# SW108_0713.net
KiCad netlist of a schematic drawn in Altium Designer
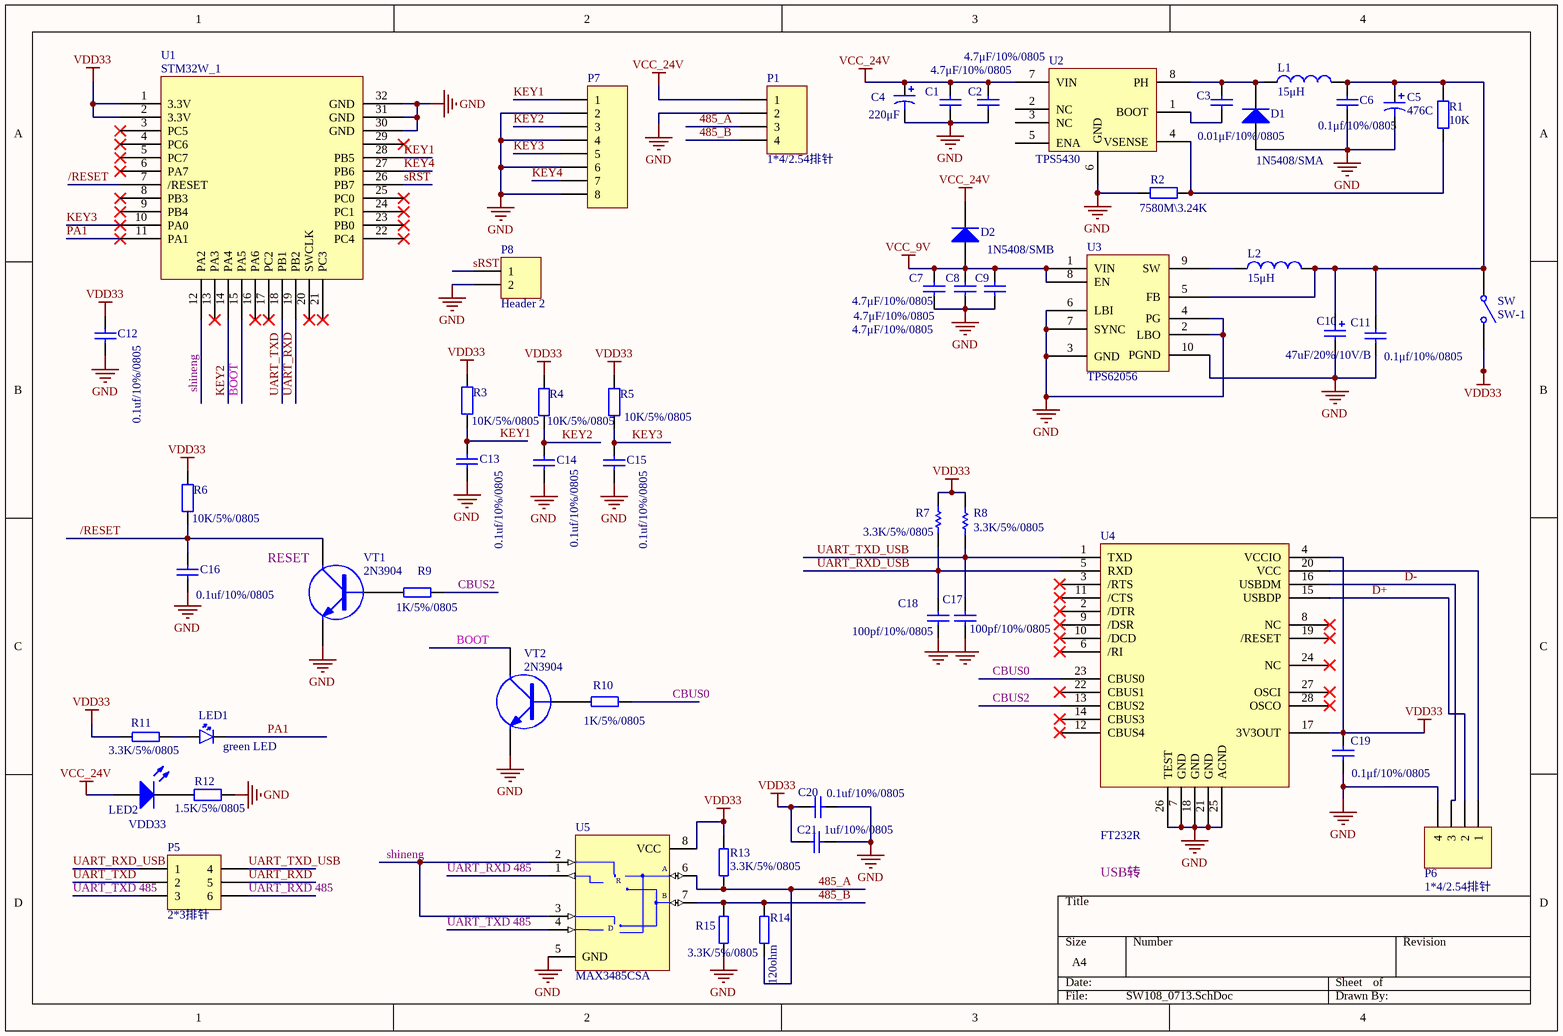
[diagram p0: SW108_0713.SchDoc]

(export (version "E")
  (design (tool "Eeschema 10.0.6"))
  (components
    (comp (ref "C1")
      (value "4.7μF/10%/0805")
      (footprint "C-0805")
      (description "Capacitor")
      (fields (field (name "PUBLISHER") "Altium Limited"))
      (libsource (lib "Miscellaneous Devices") (part "Cap"))
    )
    (comp (ref "C2")
      (value "4.7μF/10%/0805")
      (footprint "C-0805")
      (description "Capacitor")
      (fields (field (name "PUBLISHER") "Altium Limited"))
      (libsource (lib "Miscellaneous Devices") (part "Cap"))
    )
    (comp (ref "C3")
      (value "0.01μF/10%/0805")
      (footprint "C-0805")
      (description "Capacitor")
      (fields (field (name "PUBLISHER") "Altium Limited"))
      (libsource (lib "Miscellaneous Devices") (part "Cap"))
    )
    (comp (ref "C4")
      (value "220μF")
      (footprint "CZ3.0/6.5")
      (description "Polarized Capacitor (Radial)")
      (fields (field (name "PUBLISHER") "Altium Limited"))
      (libsource (lib "Miscellaneous Devices") (part "Cap Pol1"))
    )
    (comp (ref "C5")
      (value "476C")
      (footprint "C-TAN-D")
      (description "Polarized Capacitor (Radial)")
      (fields (field (name "PUBLISHER") "Altium Limited"))
      (libsource (lib "Miscellaneous Devices") (part "Cap Pol1"))
    )
    (comp (ref "C6")
      (value "0.1μf/10%/0805")
      (footprint "C-0805")
      (description "Capacitor")
      (fields (field (name "PUBLISHER") "Altium Limited"))
      (libsource (lib "Miscellaneous Devices") (part "Cap"))
    )
    (comp (ref "C7")
      (value "4.7μF/10%/0805")
      (footprint "C-0805")
      (description "Capacitor")
      (fields (field (name "PUBLISHER") "Altium Limited"))
      (libsource (lib "Miscellaneous Devices") (part "Cap"))
    )
    (comp (ref "C8")
      (value "4.7μF/10%/0805")
      (footprint "C-0805")
      (description "Capacitor")
      (fields (field (name "PUBLISHER") "Altium Limited"))
      (libsource (lib "Miscellaneous Devices") (part "Cap"))
    )
    (comp (ref "C9")
      (value "4.7μF/10%/0805")
      (footprint "C-0805")
      (description "Capacitor")
      (fields (field (name "PUBLISHER") "Altium Limited"))
      (libsource (lib "Miscellaneous Devices") (part "Cap"))
    )
    (comp (ref "C10")
      (value "47uF/20%/10V/B")
      (footprint "C-TAN-B")
      (libsource (lib "浙江关西电机数据库") (part "CAP_polarity"))
    )
    (comp (ref "C11")
      (value "0.1μf/10%/0805")
      (footprint "C-0805")
      (description "Capacitor")
      (fields (field (name "PUBLISHER") "Altium Limited"))
      (libsource (lib "Miscellaneous Devices") (part "Cap"))
    )
    (comp (ref "C12")
      (value "0.1uf/10%/0805")
      (footprint "C-0805")
      (description "Capacitor")
      (fields (field (name "PUBLISHER") "Altium Limited"))
      (libsource (lib "Miscellaneous Devices") (part "Cap"))
    )
    (comp (ref "C13")
      (value "0.1uf/10%/0805")
      (footprint "C-0805")
      (description "Capacitor")
      (fields (field (name "PUBLISHER") "Altium Limited"))
      (libsource (lib "Miscellaneous Devices") (part "Cap"))
    )
    (comp (ref "C14")
      (value "0.1uf/10%/0805")
      (footprint "C-0805")
      (description "Capacitor")
      (fields (field (name "PUBLISHER") "Altium Limited"))
      (libsource (lib "Miscellaneous Devices") (part "Cap"))
    )
    (comp (ref "C15")
      (value "0.1uf/10%/0805")
      (footprint "C-0805")
      (description "Capacitor")
      (fields (field (name "PUBLISHER") "Altium Limited"))
      (libsource (lib "Miscellaneous Devices") (part "Cap"))
    )
    (comp (ref "C16")
      (value "0.1uf/10%/0805")
      (footprint "C-0805")
      (description "Capacitor")
      (fields (field (name "PUBLISHER") "Altium Limited"))
      (libsource (lib "Miscellaneous Devices") (part "Cap"))
    )
    (comp (ref "C17")
      (value "100pf/10%/0805")
      (footprint "C-0805")
      (description "Capacitor")
      (fields (field (name "PUBLISHER") "Altium Limited"))
      (libsource (lib "Miscellaneous Devices") (part "Cap"))
    )
    (comp (ref "C18")
      (value "100pf/10%/0805")
      (footprint "C-0805")
      (description "Capacitor")
      (fields (field (name "PUBLISHER") "Altium Limited"))
      (libsource (lib "Miscellaneous Devices") (part "Cap"))
    )
    (comp (ref "C19")
      (value "0.1μf/10%/0805")
      (footprint "C-0805")
      (description "Capacitor")
      (fields (field (name "PUBLISHER") "Altium Limited"))
      (libsource (lib "Miscellaneous Devices") (part "Cap"))
    )
    (comp (ref "C20")
      (value "0.1uf/10%/0805")
      (footprint "C-0805")
      (description "Capacitor")
      (fields (field (name "PUBLISHER") "Altium Limited"))
      (libsource (lib "Miscellaneous Devices") (part "Cap"))
    )
    (comp (ref "C21")
      (value "1uf/10%/0805")
      (footprint "C-0805")
      (description "Capacitor")
      (fields (field (name "PUBLISHER") "Altium Limited"))
      (libsource (lib "Miscellaneous Devices") (part "Cap"))
    )
    (comp (ref "D1")
      (value "1N5408/SMA")
      (footprint "SMA 2+")
      (description "3 Amp Medium Power Silicon Rectifier Diode")
      (fields (field (name "PUBLISHER") "Altium Limited"))
      (libsource (lib "Miscellaneous Devices") (part "Diode 1N5408"))
    )
    (comp (ref "D2")
      (value "1N5408/SMB")
      (footprint "smb")
      (description "3 Amp Medium Power Silicon Rectifier Diode")
      (fields (field (name "PUBLISHER") "Altium Limited"))
      (libsource (lib "Miscellaneous Devices") (part "Diode 1N5408"))
    )
    (comp (ref "L1")
      (value "15μH")
      (footprint "GSDS104C2")
      (description "Inductor")
      (fields (field (name "PUBLISHER") "Altium Limited"))
      (libsource (lib "Miscellaneous Devices") (part "Inductor"))
    )
    (comp (ref "L2")
      (value "15μH")
      (footprint "GSDS104C2")
      (description "Inductor")
      (fields (field (name "PUBLISHER") "Altium Limited"))
      (libsource (lib "Miscellaneous Devices") (part "Inductor"))
    )
    (comp (ref "LED1") (value "green LED") (footprint "LED-φ3") (libsource (lib "Haze") (part "LED")))
    (comp (ref "LED2")
      (value "VDD33")
      (footprint "LED-φ3")
      (description "Typical BLUE SiC LED")
      (fields (field (name "PUBLISHER") "Altium Limited"))
      (libsource (lib "Miscellaneous Devices") (part "LED3"))
    )
    (comp (ref "P1")
      (value "1*4/2.54排针")
      (footprint "PIN-S-2.54-1*4")
      (description "Header, 4-Pin")
      (fields (field (name "PUBLISHER") "Altium Limited"))
      (libsource (lib "") (part "Header 4_1"))
    )
    (comp (ref "P5")
      (value "2*3排针")
      (footprint "HDR2X3_CEN")
      (description "Header, 3-Pin, Dual row")
      (fields (field (name "PUBLISHER") "Altium Limited"))
      (libsource (lib "Miscellaneous Connectors") (part "Header 3X2A"))
    )
    (comp (ref "P6")
      (value "1*4/2.54排针")
      (footprint "PIN-S-2.54-1*4")
      (description "Header, 4-Pin")
      (fields (field (name "PUBLISHER") "Altium Limited"))
      (libsource (lib "Miscellaneous Connectors") (part "Header 4"))
    )
    (comp (ref "P7")
      (value "Header 8")
      (footprint "HDR1X8")
      (description "Header, 8-Pin")
      (fields (field (name "PUBLISHER") "Altium Limited"))
      (libsource (lib "Miscellaneous Connectors") (part "Header 8"))
    )
    (comp (ref "P8")
      (value "Header 2")
      (footprint "HDR1X2")
      (description "Header, 2-Pin")
      (fields (field (name "PUBLISHER") "Altium Limited"))
      (libsource (lib "Miscellaneous Connectors") (part "Header 2"))
    )
    (comp (ref "R1")
      (value "10K")
      (footprint "R-0805")
      (description "Resistor")
      (fields (field (name "PUBLISHER") "Altium Limited"))
      (libsource (lib "Miscellaneous Devices") (part "Res2"))
    )
    (comp (ref "R2")
      (value "7580~{M}3.24K")
      (footprint "R-0805")
      (description "Resistor")
      (fields (field (name "PUBLISHER") "Altium Limited"))
      (libsource (lib "") (part "Res2_1"))
    )
    (comp (ref "R3")
      (value "10K/5%/0805")
      (footprint "R-0805")
      (description "Resistor")
      (fields (field (name "PUBLISHER") "Altium Limited"))
      (libsource (lib "Miscellaneous Devices") (part "Res2"))
    )
    (comp (ref "R4")
      (value "10K/5%/0805")
      (footprint "R-0805")
      (description "Resistor")
      (fields (field (name "PUBLISHER") "Altium Limited"))
      (libsource (lib "Miscellaneous Devices") (part "Res2"))
    )
    (comp (ref "R5")
      (value "10K/5%/0805")
      (footprint "R-0805")
      (description "Resistor")
      (fields (field (name "PUBLISHER") "Altium Limited"))
      (libsource (lib "Miscellaneous Devices") (part "Res2"))
    )
    (comp (ref "R6")
      (value "10K/5%/0805")
      (footprint "R-0805")
      (description "Resistor")
      (fields (field (name "PUBLISHER") "Altium Limited"))
      (libsource (lib "Miscellaneous Devices") (part "Res2"))
    )
    (comp (ref "R7")
      (value "3.3K/5%/0805")
      (footprint "R-0805")
      (libsource (lib "SCHLIBRARIES") (part "RES_1"))
    )
    (comp (ref "R8")
      (value "3.3K/5%/0805")
      (footprint "R-0805")
      (libsource (lib "SCHLIBRARIES") (part "RES_1"))
    )
    (comp (ref "R9")
      (value "1K/5%/0805")
      (footprint "R-0805")
      (description "R")
      (libsource (lib "Haze") (part "RES"))
    )
    (comp (ref "R10")
      (value "1K/5%/0805")
      (footprint "R-0805")
      (description "R")
      (libsource (lib "Haze") (part "RES"))
    )
    (comp (ref "R11")
      (value "3.3K/5%/0805")
      (footprint "R-0805")
      (description "R")
      (libsource (lib "Haze") (part "RES"))
    )
    (comp (ref "R12")
      (value "1.5K/5%/0805")
      (footprint "R-0805")
      (description "Resistor")
      (fields (field (name "PUBLISHER") "Altium Limited"))
      (libsource (lib "") (part "Res2_1"))
    )
    (comp (ref "R13")
      (value "3.3K/5%/0805")
      (footprint "R-0805")
      (description "R")
      (libsource (lib "Haze") (part "RES"))
    )
    (comp (ref "R14")
      (value "120ohm")
      (footprint "R-0805")
      (description "R")
      (libsource (lib "Haze") (part "RES"))
    )
    (comp (ref "R15")
      (value "3.3K/5%/0805")
      (footprint "R-0805")
      (description "R")
      (libsource (lib "Haze") (part "RES"))
    )
    (comp (ref "SW")
      (value "SW-1")
      (footprint "PIN-S-2.54-1*2")
      (libsource (lib "SCHLIBRARIES") (part "SW-1"))
    )
    (comp (ref "U1")
      (value "STM32W_1")
      (footprint "STM32W108-3")
      (libsource (lib "STM32W108-3") (part "STM32W108-3"))
    )
    (comp (ref "U2") (value "TPS5430") (footprint "SO-G8") (libsource (lib "SCHLIBRARIES") (part "TPS5430")))
    (comp (ref "U3")
      (value "TPS62056")
      (footprint "MSOP-10")
      (libsource (lib "SCHLIBRARIES") (part "TPS62056"))
    )
    (comp (ref "U4") (value "FT232R") (footprint "SSOP-28") (libsource (lib "Haze") (part "FT232R")))
    (comp (ref "U5")
      (value "MAX3485CSA")
      (footprint "SO-G8")
      (description "Low-Power, Slew-Rate-Limited RS-485/RS-422 Transceiver")
      (fields (field (name "PUBLISHER") "Altium Limited"))
      (libsource (lib "Maxim Communication Transceiver") (part "MAX485CSA"))
    )
    (comp (ref "VT1")
      (value "2N3904")
      (footprint "SOT23-3")
      (description "NPN Transistor")
      (libsource (lib "Haze") (part "NPN"))
    )
    (comp (ref "VT2")
      (value "2N3904")
      (footprint "SOT23-3")
      (description "NPN Transistor")
      (libsource (lib "Haze") (part "NPN"))
    )
  )
  (nets
    (net (code "1") (name "/485_A") (class "Default")
      (node (ref "P1") (pin "3") (pinfunction "3_3") (pintype "passive"))
      (node (ref "R13") (pin "1") (pinfunction "1_1") (pintype "passive"))
      (node (ref "R14") (pin "2") (pinfunction "2_2") (pintype "passive"))
      (node (ref "U5") (pin "6") (pinfunction "A_6") (pintype "bidirectional"))
    )
    (net (code "2") (name "/485_B") (class "Default")
      (node (ref "P1") (pin "4") (pinfunction "4_4") (pintype "passive"))
      (node (ref "R14") (pin "1") (pinfunction "1_1") (pintype "passive"))
      (node (ref "R15") (pin "2") (pinfunction "2_2") (pintype "passive"))
      (node (ref "U5") (pin "7") (pinfunction "B_7") (pintype "bidirectional"))
    )
    (net (code "3") (name "/BOOT") (class "Default")
      (node (ref "U1") (pin "15") (pinfunction "PA5_15") (pintype "passive"))
      (node (ref "VT2") (pin "3") (pinfunction "C_3") (pintype "passive"))
    )
    (net (code "4") (name "/CBUS0") (class "Default")
      (node (ref "R10") (pin "2") (pinfunction "2_2") (pintype "passive"))
      (node (ref "U4") (pin "23") (pinfunction "CBUS0_23") (pintype "passive"))
    )
    (net (code "5") (name "/CBUS2") (class "Default")
      (node (ref "R9") (pin "2") (pinfunction "2_2") (pintype "passive"))
      (node (ref "U4") (pin "13") (pinfunction "CBUS2_13") (pintype "passive"))
    )
    (net (code "6") (name "/D+") (class "Default")
      (node (ref "P6") (pin "2") (pinfunction "2_2") (pintype "passive"))
      (node (ref "U4") (pin "15") (pinfunction "USBDP_15") (pintype "passive"))
    )
    (net (code "7") (name "/D-") (class "Default")
      (node (ref "P6") (pin "3") (pinfunction "3_3") (pintype "passive"))
      (node (ref "U4") (pin "16") (pinfunction "USBDM_16") (pintype "passive"))
    )
    (net (code "8") (name "/KEY1") (class "Default")
      (node (ref "C13") (pin "2") (pinfunction "2_2") (pintype "passive"))
      (node (ref "P7") (pin "1") (pinfunction "1_1") (pintype "passive"))
      (node (ref "R3") (pin "1") (pinfunction "1_1") (pintype "passive"))
      (node (ref "U1") (pin "28") (pinfunction "PB5_28") (pintype "passive"))
    )
    (net (code "9") (name "/KEY2") (class "Default")
      (node (ref "C14") (pin "2") (pinfunction "2_2") (pintype "passive"))
      (node (ref "P7") (pin "3") (pinfunction "3_3") (pintype "passive"))
      (node (ref "R4") (pin "1") (pinfunction "1_1") (pintype "passive"))
      (node (ref "U1") (pin "14") (pinfunction "PA4_14") (pintype "passive"))
    )
    (net (code "10") (name "/KEY3") (class "Default")
      (node (ref "C15") (pin "2") (pinfunction "2_2") (pintype "passive"))
      (node (ref "P7") (pin "5") (pinfunction "5_5") (pintype "passive"))
      (node (ref "R5") (pin "1") (pinfunction "1_1") (pintype "passive"))
      (node (ref "U1") (pin "10") (pinfunction "PA0_10") (pintype "passive"))
    )
    (net (code "11") (name "/KEY4") (class "Default")
      (node (ref "P7") (pin "7") (pinfunction "7_7") (pintype "passive"))
      (node (ref "U1") (pin "27") (pinfunction "PB6_27") (pintype "passive"))
    )
    (net (code "12") (name "/PA1") (class "Default")
      (node (ref "LED1") (pin "2") (pinfunction "K_2") (pintype "passive"))
      (node (ref "U1") (pin "11") (pinfunction "PA1_11") (pintype "passive"))
    )
    (net (code "13") (name "/UART_RXD") (class "Default")
      (node (ref "P5") (pin "5") (pinfunction "5_5") (pintype "passive"))
      (node (ref "U1") (pin "19") (pinfunction "PB2_19") (pintype "passive"))
    )
    (net (code "14") (name "/UART_RXD 485") (class "Default")
      (node (ref "P5") (pin "6") (pinfunction "6_6") (pintype "passive"))
      (node (ref "U5") (pin "1") (pinfunction "RO_1") (pintype "output"))
    )
    (net (code "15") (name "/UART_RXD_USB") (class "Default")
      (node (ref "C18") (pin "2") (pinfunction "2_2") (pintype "passive"))
      (node (ref "P5") (pin "1") (pinfunction "1_1") (pintype "passive"))
      (node (ref "R7") (pin "1") (pinfunction "1_1") (pintype "passive"))
      (node (ref "U4") (pin "5") (pinfunction "RXD_5") (pintype "passive"))
    )
    (net (code "16") (name "/UART_TXD") (class "Default")
      (node (ref "P5") (pin "2") (pinfunction "2_2") (pintype "passive"))
      (node (ref "U1") (pin "18") (pinfunction "PB1_18") (pintype "passive"))
    )
    (net (code "17") (name "/UART_TXD 485") (class "Default")
      (node (ref "P5") (pin "3") (pinfunction "3_3") (pintype "passive"))
      (node (ref "U5") (pin "4") (pinfunction "DI_4") (pintype "input"))
    )
    (net (code "18") (name "/UART_TXD_USB") (class "Default")
      (node (ref "C17") (pin "2") (pinfunction "2_2") (pintype "passive"))
      (node (ref "P5") (pin "4") (pinfunction "4_4") (pintype "passive"))
      (node (ref "R8") (pin "1") (pinfunction "1_1") (pintype "passive"))
      (node (ref "U4") (pin "1") (pinfunction "TXD_1") (pintype "passive"))
    )
    (net (code "19") (name "/sRST") (class "Default")
      (node (ref "P8") (pin "1") (pinfunction "1_1") (pintype "passive"))
      (node (ref "U1") (pin "26") (pinfunction "PB7_26") (pintype "passive"))
    )
    (net (code "20") (name "/shineng") (class "Default")
      (node (ref "U1") (pin "12") (pinfunction "PA2_12") (pintype "passive"))
      (node (ref "U5") (pin "2") (pinfunction "~{RE}_2") (pintype "input"))
      (node (ref "U5") (pin "3") (pinfunction "DE_3") (pintype "input"))
    )
    (net (code "21") (name "/{slash}RESET") (class "Default")
      (node (ref "C16") (pin "2") (pinfunction "2_2") (pintype "passive"))
      (node (ref "R6") (pin "1") (pinfunction "1_1") (pintype "passive"))
      (node (ref "U1") (pin "7") (pinfunction "/RESET_7") (pintype "passive"))
      (node (ref "VT1") (pin "3") (pinfunction "C_3") (pintype "passive"))
    )
    (net (code "22") (name "GND") (class "Default")
      (node (ref "C1") (pin "1") (pinfunction "1_1") (pintype "passive"))
      (node (ref "C10") (pin "2") (pinfunction "2_2") (pintype "passive"))
      (node (ref "C11") (pin "1") (pinfunction "1_1") (pintype "passive"))
      (node (ref "C12") (pin "1") (pinfunction "1_1") (pintype "passive"))
      (node (ref "C13") (pin "1") (pinfunction "1_1") (pintype "passive"))
      (node (ref "C14") (pin "1") (pinfunction "1_1") (pintype "passive"))
      (node (ref "C15") (pin "1") (pinfunction "1_1") (pintype "passive"))
      (node (ref "C16") (pin "1") (pinfunction "1_1") (pintype "passive"))
      (node (ref "C17") (pin "1") (pinfunction "1_1") (pintype "passive"))
      (node (ref "C18") (pin "1") (pinfunction "1_1") (pintype "passive"))
      (node (ref "C19") (pin "1") (pinfunction "1_1") (pintype "passive"))
      (node (ref "C2") (pin "1") (pinfunction "1_1") (pintype "passive"))
      (node (ref "C20") (pin "1") (pinfunction "1_1") (pintype "passive"))
      (node (ref "C21") (pin "1") (pinfunction "1_1") (pintype "passive"))
      (node (ref "C4") (pin "2") (pinfunction "2_2") (pintype "passive"))
      (node (ref "C5") (pin "2") (pinfunction "2_2") (pintype "passive"))
      (node (ref "C6") (pin "1") (pinfunction "1_1") (pintype "passive"))
      (node (ref "C7") (pin "1") (pinfunction "1_1") (pintype "passive"))
      (node (ref "C8") (pin "1") (pinfunction "1_1") (pintype "passive"))
      (node (ref "C9") (pin "1") (pinfunction "1_1") (pintype "passive"))
      (node (ref "D1") (pin "1") (pinfunction "A_1") (pintype "passive"))
      (node (ref "P1") (pin "2") (pinfunction "2_2") (pintype "passive"))
      (node (ref "P6") (pin "4") (pinfunction "4_4") (pintype "passive"))
      (node (ref "P7") (pin "2") (pinfunction "2_2") (pintype "passive"))
      (node (ref "P7") (pin "4") (pinfunction "4_4") (pintype "passive"))
      (node (ref "P7") (pin "6") (pinfunction "6_6") (pintype "passive"))
      (node (ref "P7") (pin "8") (pinfunction "8_8") (pintype "passive"))
      (node (ref "P8") (pin "2") (pinfunction "2_2") (pintype "passive"))
      (node (ref "R12") (pin "1") (pinfunction "1_1") (pintype "passive"))
      (node (ref "R15") (pin "1") (pinfunction "1_1") (pintype "passive"))
      (node (ref "R2") (pin "2") (pinfunction "2_2") (pintype "passive"))
      (node (ref "U1") (pin "30") (pinfunction "GND_30") (pintype "passive"))
      (node (ref "U1") (pin "31") (pinfunction "GND_31") (pintype "passive"))
      (node (ref "U1") (pin "32") (pinfunction "GND_32") (pintype "passive"))
      (node (ref "U2") (pin "6") (pinfunction "GND_6") (pintype "passive"))
      (node (ref "U3") (pin "10") (pinfunction "PGND_10") (pintype "passive"))
      (node (ref "U3") (pin "2") (pinfunction "LBO_2") (pintype "passive"))
      (node (ref "U3") (pin "3") (pinfunction "GND_3") (pintype "passive"))
      (node (ref "U3") (pin "4") (pinfunction "PG_4") (pintype "passive"))
      (node (ref "U3") (pin "6") (pinfunction "LBI_6") (pintype "passive"))
      (node (ref "U3") (pin "7") (pinfunction "SYNC_7") (pintype "passive"))
      (node (ref "U4") (pin "18") (pinfunction "GND_18") (pintype "passive"))
      (node (ref "U4") (pin "21") (pinfunction "GND_21") (pintype "passive"))
      (node (ref "U4") (pin "25") (pinfunction "AGND_25") (pintype "passive"))
      (node (ref "U4") (pin "26") (pinfunction "TEST_26") (pintype "passive"))
      (node (ref "U4") (pin "7") (pinfunction "GND_7") (pintype "passive"))
      (node (ref "U5") (pin "5") (pinfunction "GND_5") (pintype "power_in"))
      (node (ref "VT1") (pin "2") (pinfunction "E_2") (pintype "passive"))
      (node (ref "VT2") (pin "2") (pinfunction "E_2") (pintype "passive"))
    )
    (net (code "23") (name "Net-(D1-K)") (class "Default")
      (node (ref "C3") (pin "2") (pinfunction "2_2") (pintype "passive"))
      (node (ref "D1") (pin "2") (pinfunction "K_2") (pintype "passive"))
      (node (ref "L1") (pin "1") (pinfunction "1_1") (pintype "passive"))
      (node (ref "U2") (pin "8") (pinfunction "PH_8") (pintype "passive"))
    )
    (net (code "24") (name "Net-(LED1-A)") (class "Default")
      (node (ref "LED1") (pin "1") (pinfunction "A_1") (pintype "passive"))
      (node (ref "R11") (pin "2") (pinfunction "2_2") (pintype "passive"))
    )
    (net (code "25") (name "Net-(LED2-K)") (class "Default")
      (node (ref "LED2") (pin "2") (pinfunction "K_2") (pintype "passive"))
      (node (ref "R12") (pin "2") (pinfunction "2_2") (pintype "passive"))
    )
    (net (code "26") (name "Net-(U2-BOOT)") (class "Default")
      (node (ref "C3") (pin "1") (pinfunction "1_1") (pintype "passive"))
      (node (ref "U2") (pin "1") (pinfunction "BOOT_1") (pintype "passive"))
    )
    (net (code "27") (name "Net-(U2-VSENSE)") (class "Default")
      (node (ref "R1") (pin "1") (pinfunction "1_1") (pintype "passive"))
      (node (ref "R2") (pin "1") (pinfunction "1_1") (pintype "passive"))
      (node (ref "U2") (pin "4") (pinfunction "VSENSE_4") (pintype "passive"))
    )
    (net (code "28") (name "Net-(U3-FB)") (class "Default")
      (node (ref "C10") (pin "1") (pinfunction "1_1") (pintype "passive"))
      (node (ref "C11") (pin "2") (pinfunction "2_2") (pintype "passive"))
      (node (ref "C5") (pin "1") (pinfunction "1_1") (pintype "passive"))
      (node (ref "C6") (pin "2") (pinfunction "2_2") (pintype "passive"))
      (node (ref "L1") (pin "2") (pinfunction "2_2") (pintype "passive"))
      (node (ref "L2") (pin "2") (pinfunction "2_2") (pintype "passive"))
      (node (ref "R1") (pin "2") (pinfunction "2_2") (pintype "passive"))
      (node (ref "SW") (pin "1") (pinfunction "1_1") (pintype "passive"))
      (node (ref "U3") (pin "5") (pinfunction "FB_5") (pintype "passive"))
    )
    (net (code "29") (name "Net-(U3-SW)") (class "Default")
      (node (ref "L2") (pin "1") (pinfunction "1_1") (pintype "passive"))
      (node (ref "U3") (pin "9") (pinfunction "SW_9") (pintype "passive"))
    )
    (net (code "30") (name "Net-(U4-VCC)") (class "Default")
      (node (ref "P6") (pin "1") (pinfunction "1_1") (pintype "passive"))
      (node (ref "U4") (pin "20") (pinfunction "VCC_20") (pintype "passive"))
    )
    (net (code "31") (name "Net-(VT1-B)") (class "Default")
      (node (ref "R9") (pin "1") (pinfunction "1_1") (pintype "passive"))
      (node (ref "VT1") (pin "1") (pinfunction "B_1") (pintype "passive"))
    )
    (net (code "32") (name "Net-(VT2-B)") (class "Default")
      (node (ref "R10") (pin "1") (pinfunction "1_1") (pintype "passive"))
      (node (ref "VT2") (pin "1") (pinfunction "B_1") (pintype "passive"))
    )
    (net (code "33") (name "VCC_9V") (class "Default")
      (node (ref "C7") (pin "2") (pinfunction "2_2") (pintype "passive"))
      (node (ref "C8") (pin "2") (pinfunction "2_2") (pintype "passive"))
      (node (ref "C9") (pin "2") (pinfunction "2_2") (pintype "passive"))
      (node (ref "D2") (pin "1") (pinfunction "A_1") (pintype "passive"))
      (node (ref "U3") (pin "1") (pinfunction "VIN_1") (pintype "passive"))
      (node (ref "U3") (pin "8") (pinfunction "EN_8") (pintype "passive"))
    )
    (net (code "34") (name "VCC_24V") (class "Default")
      (node (ref "C1") (pin "2") (pinfunction "2_2") (pintype "passive"))
      (node (ref "C2") (pin "2") (pinfunction "2_2") (pintype "passive"))
      (node (ref "C4") (pin "1") (pinfunction "1_1") (pintype "passive"))
      (node (ref "D2") (pin "2") (pinfunction "K_2") (pintype "passive"))
      (node (ref "LED2") (pin "1") (pinfunction "A_1") (pintype "passive"))
      (node (ref "P1") (pin "1") (pinfunction "1_1") (pintype "passive"))
      (node (ref "U2") (pin "7") (pinfunction "VIN_7") (pintype "passive"))
    )
    (net (code "35") (name "VDD33") (class "Default")
      (node (ref "C12") (pin "2") (pinfunction "2_2") (pintype "passive"))
      (node (ref "C19") (pin "2") (pinfunction "2_2") (pintype "passive"))
      (node (ref "C20") (pin "2") (pinfunction "2_2") (pintype "passive"))
      (node (ref "C21") (pin "2") (pinfunction "2_2") (pintype "passive"))
      (node (ref "R11") (pin "1") (pinfunction "1_1") (pintype "passive"))
      (node (ref "R13") (pin "2") (pinfunction "2_2") (pintype "passive"))
      (node (ref "R3") (pin "2") (pinfunction "2_2") (pintype "passive"))
      (node (ref "R4") (pin "2") (pinfunction "2_2") (pintype "passive"))
      (node (ref "R5") (pin "2") (pinfunction "2_2") (pintype "passive"))
      (node (ref "R6") (pin "2") (pinfunction "2_2") (pintype "passive"))
      (node (ref "R7") (pin "2") (pinfunction "2_2") (pintype "passive"))
      (node (ref "R8") (pin "2") (pinfunction "2_2") (pintype "passive"))
      (node (ref "SW") (pin "2") (pinfunction "2_2") (pintype "passive"))
      (node (ref "U1") (pin "1") (pinfunction "3.3V_1") (pintype "passive"))
      (node (ref "U1") (pin "2") (pinfunction "3.3V_2") (pintype "passive"))
      (node (ref "U4") (pin "17") (pinfunction "3V3OUT_17") (pintype "passive"))
      (node (ref "U4") (pin "4") (pinfunction "VCCIO_4") (pintype "passive"))
      (node (ref "U5") (pin "8") (pinfunction "VCC_8") (pintype "power_in"))
    )
    (net (code "36") (name "unconnected-(U1-PA3-Pad13)") (class "Default")
      (node (ref "U1") (pin "13") (pinfunction "PA3_13") (pintype "passive+no_connect"))
    )
    (net (code "37") (name "unconnected-(U1-PA6-Pad16)") (class "Default")
      (node (ref "U1") (pin "16") (pinfunction "PA6_16") (pintype "passive+no_connect"))
    )
    (net (code "38") (name "unconnected-(U1-PA7-Pad6)") (class "Default")
      (node (ref "U1") (pin "6") (pinfunction "PA7_6") (pintype "passive+no_connect"))
    )
    (net (code "39") (name "unconnected-(U1-PB0-Pad23)") (class "Default")
      (node (ref "U1") (pin "23") (pinfunction "PB0_23") (pintype "passive+no_connect"))
    )
    (net (code "40") (name "unconnected-(U1-PB3-Pad8)") (class "Default")
      (node (ref "U1") (pin "8") (pinfunction "PB3_8") (pintype "passive+no_connect"))
    )
    (net (code "41") (name "unconnected-(U1-PB4-Pad9)") (class "Default")
      (node (ref "U1") (pin "9") (pinfunction "PB4_9") (pintype "passive+no_connect"))
    )
    (net (code "42") (name "unconnected-(U1-PC0-Pad25)") (class "Default")
      (node (ref "U1") (pin "25") (pinfunction "PC0_25") (pintype "passive+no_connect"))
    )
    (net (code "43") (name "unconnected-(U1-PC1-Pad24)") (class "Default")
      (node (ref "U1") (pin "24") (pinfunction "PC1_24") (pintype "passive+no_connect"))
    )
    (net (code "44") (name "unconnected-(U1-PC2-Pad17)") (class "Default")
      (node (ref "U1") (pin "17") (pinfunction "PC2_17") (pintype "passive+no_connect"))
    )
    (net (code "45") (name "unconnected-(U1-PC3-Pad21)") (class "Default")
      (node (ref "U1") (pin "21") (pinfunction "PC3_21") (pintype "passive+no_connect"))
    )
    (net (code "46") (name "unconnected-(U1-PC4-Pad22)") (class "Default")
      (node (ref "U1") (pin "22") (pinfunction "PC4_22") (pintype "passive+no_connect"))
    )
    (net (code "47") (name "unconnected-(U1-PC5-Pad3)") (class "Default")
      (node (ref "U1") (pin "3") (pinfunction "PC5_3") (pintype "passive+no_connect"))
    )
    (net (code "48") (name "unconnected-(U1-PC6-Pad4)") (class "Default")
      (node (ref "U1") (pin "4") (pinfunction "PC6_4") (pintype "passive+no_connect"))
    )
    (net (code "49") (name "unconnected-(U1-PC7-Pad5)") (class "Default")
      (node (ref "U1") (pin "5") (pinfunction "PC7_5") (pintype "passive+no_connect"))
    )
    (net (code "50") (name "unconnected-(U1-Pad29)") (class "Default")
      (node (ref "U1") (pin "29") (pintype "passive+no_connect"))
    )
    (net (code "51") (name "unconnected-(U1-SWCLK-Pad20)") (class "Default")
      (node (ref "U1") (pin "20") (pinfunction "SWCLK_20") (pintype "passive+no_connect"))
    )
    (net (code "52") (name "unconnected-(U2-ENA-Pad5)") (class "Default")
      (node (ref "U2") (pin "5") (pinfunction "ENA_5") (pintype "passive"))
    )
    (net (code "53") (name "unconnected-(U2-NC-Pad2)") (class "Default")
      (node (ref "U2") (pin "2") (pinfunction "NC_2") (pintype "passive"))
    )
    (net (code "54") (name "unconnected-(U2-NC-Pad3)") (class "Default")
      (node (ref "U2") (pin "3") (pinfunction "NC_3") (pintype "passive"))
    )
    (net (code "55") (name "unconnected-(U4-CBUS1-Pad22)") (class "Default")
      (node (ref "U4") (pin "22") (pinfunction "CBUS1_22") (pintype "passive+no_connect"))
    )
    (net (code "56") (name "unconnected-(U4-CBUS3-Pad14)") (class "Default")
      (node (ref "U4") (pin "14") (pinfunction "CBUS3_14") (pintype "passive+no_connect"))
    )
    (net (code "57") (name "unconnected-(U4-CBUS4-Pad12)") (class "Default")
      (node (ref "U4") (pin "12") (pinfunction "CBUS4_12") (pintype "passive+no_connect"))
    )
    (net (code "58") (name "unconnected-(U4-NC-Pad8)") (class "Default")
      (node (ref "U4") (pin "8") (pinfunction "NC_8") (pintype "passive+no_connect"))
    )
    (net (code "59") (name "unconnected-(U4-NC-Pad24)") (class "Default")
      (node (ref "U4") (pin "24") (pinfunction "NC_24") (pintype "passive+no_connect"))
    )
    (net (code "60") (name "unconnected-(U4-OSCI-Pad27)") (class "Default")
      (node (ref "U4") (pin "27") (pinfunction "OSCI_27") (pintype "passive+no_connect"))
    )
    (net (code "61") (name "unconnected-(U4-OSCO-Pad28)") (class "Default")
      (node (ref "U4") (pin "28") (pinfunction "OSCO_28") (pintype "passive+no_connect"))
    )
    (net (code "62") (name "unconnected-(U4-{slash}CTS-Pad11)") (class "Default")
      (node (ref "U4") (pin "11") (pinfunction "/CTS_11") (pintype "passive+no_connect"))
    )
    (net (code "63") (name "unconnected-(U4-{slash}DCD-Pad10)") (class "Default")
      (node (ref "U4") (pin "10") (pinfunction "/DCD_10") (pintype "passive+no_connect"))
    )
    (net (code "64") (name "unconnected-(U4-{slash}DSR-Pad9)") (class "Default")
      (node (ref "U4") (pin "9") (pinfunction "/DSR_9") (pintype "passive+no_connect"))
    )
    (net (code "65") (name "unconnected-(U4-{slash}DTR-Pad2)") (class "Default")
      (node (ref "U4") (pin "2") (pinfunction "/DTR_2") (pintype "passive+no_connect"))
    )
    (net (code "66") (name "unconnected-(U4-{slash}RESET-Pad19)") (class "Default")
      (node (ref "U4") (pin "19") (pinfunction "/RESET_19") (pintype "passive+no_connect"))
    )
    (net (code "67") (name "unconnected-(U4-{slash}RI-Pad6)") (class "Default")
      (node (ref "U4") (pin "6") (pinfunction "/RI_6") (pintype "passive+no_connect"))
    )
    (net (code "68") (name "unconnected-(U4-{slash}RTS-Pad3)") (class "Default")
      (node (ref "U4") (pin "3") (pinfunction "/RTS_3") (pintype "passive+no_connect"))
    )
  )
)
